# plant_long_life_v1_00.net
KiCad netlist of a schematic drawn in EAGLE
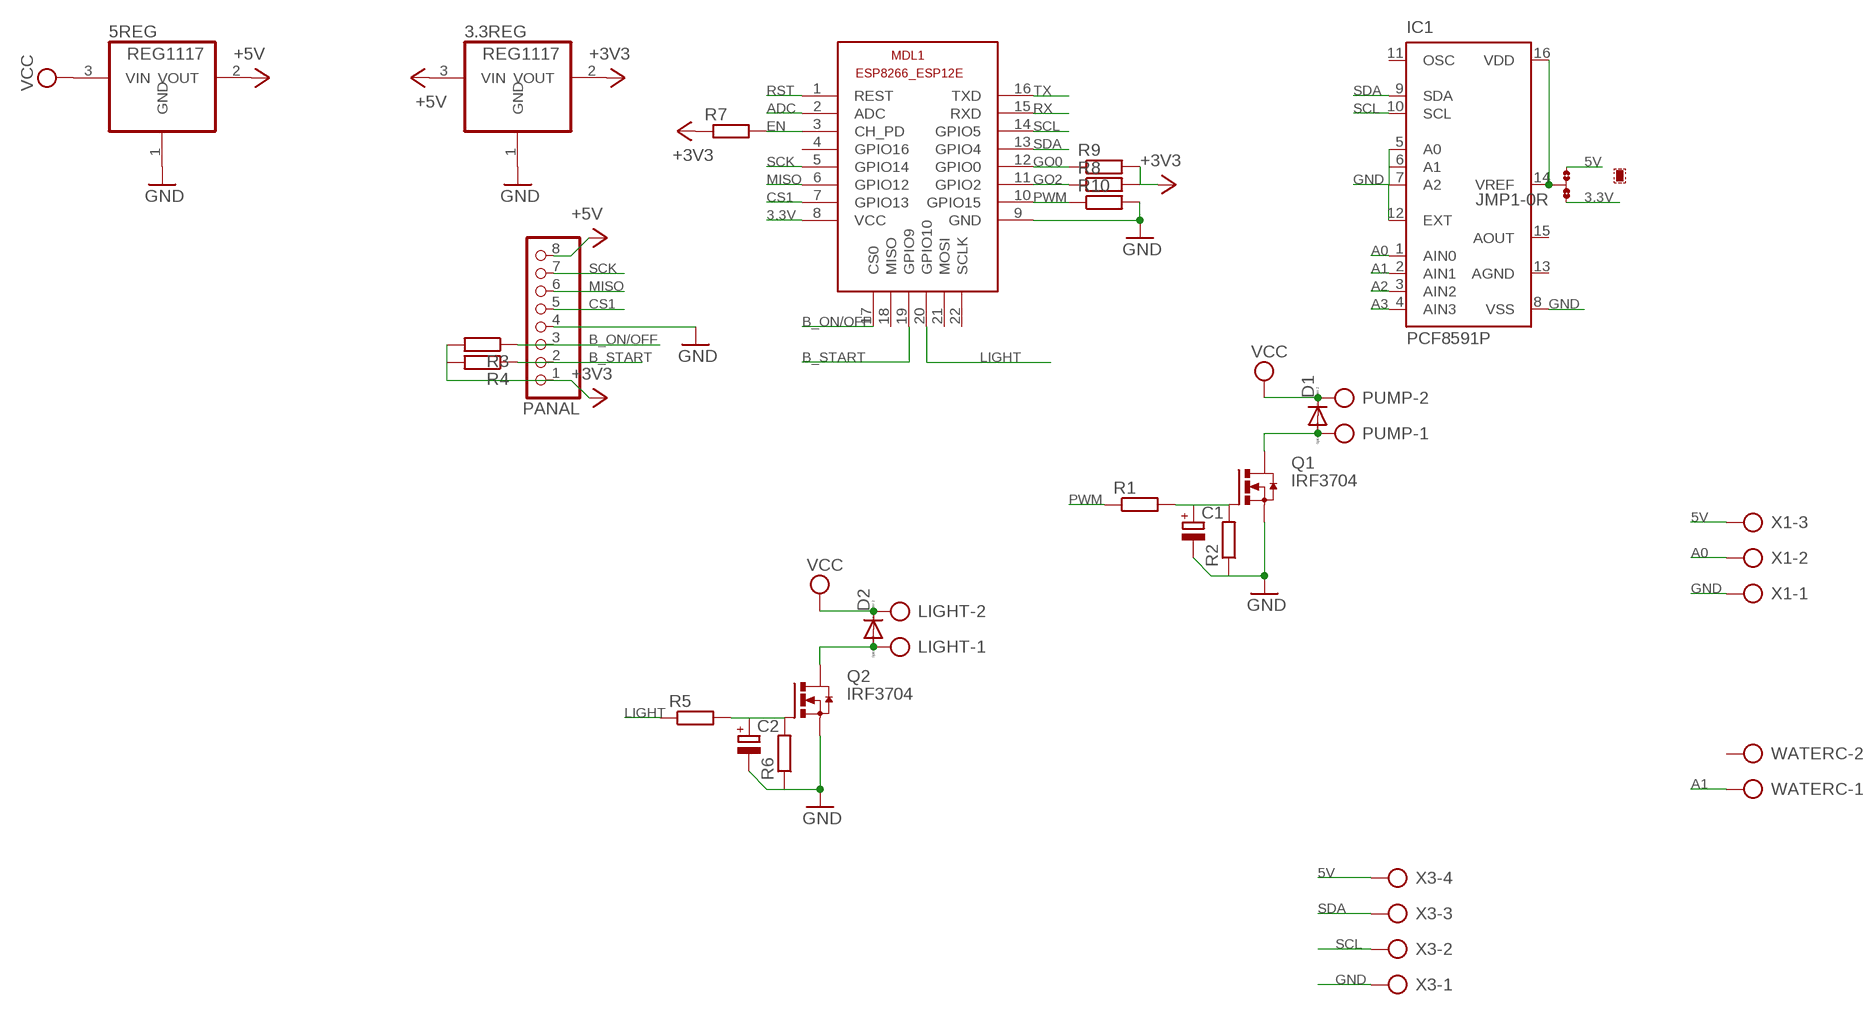
[diagram p0: schematic, sheet 1]

(export (version "E")
  (design (tool "Eeschema 10.0.6"))
  (components
    (comp (ref "3.3REG")
      (value "REG1117")
      (footprint "eagle-import:SOT223")
      (libsource (lib "eagle-import") (part "REG1117"))
    )
    (comp (ref "5REG")
      (value "REG1117")
      (footprint "eagle-import:SOT223")
      (libsource (lib "eagle-import") (part "REG1117"))
    )
    (comp (ref "C1")
      (value "CPOL-EUSMCA")
      (footprint "eagle-import:SMC_A")
      (libsource (lib "eagle-import") (part "CPOL-EUSMCA"))
    )
    (comp (ref "C2")
      (value "CPOL-EUSMCA")
      (footprint "eagle-import:SMC_A")
      (libsource (lib "eagle-import") (part "CPOL-EUSMCA"))
    )
    (comp (ref "D1")
      (value "DIODE-SMC")
      (footprint "eagle-import:SMC")
      (libsource (lib "eagle-import") (part "DIODE-SMC"))
    )
    (comp (ref "D2")
      (value "DIODE-SMC")
      (footprint "eagle-import:SMC")
      (libsource (lib "eagle-import") (part "DIODE-SMC"))
    )
    (comp (ref "IC1")
      (value "PCF8591P")
      (footprint "eagle-import:DIL16")
      (fields (field (name "MF") "FARNELL"))
      (libsource (lib "eagle-import") (part "PCF8591P"))
    )
    (comp (ref "JMP1")
      (value "0R-JUMPA")
      (footprint "eagle-import:A0R-JMP")
      (libsource (lib "eagle-import") (part "0R-JUMPA"))
    )
    (comp (ref "LIGHT")
      (value "AK300/2")
      (footprint "eagle-import:AK300_2")
      (libsource (lib "eagle-import") (part "AK300/2"))
    )
    (comp (ref "MDL1")
      (value "ESP8266-12EESP8266-ESP12E")
      (footprint "eagle-import:ESP8266-ESP12E")
      (libsource (lib "eagle-import") (part "ESP8266-12EESP8266-ESP12E"))
    )
    (comp (ref "PANAL")
      (value "PINHD-1X8")
      (footprint "eagle-import:1X08")
      (libsource (lib "eagle-import") (part "PINHD-1X8"))
    )
    (comp (ref "PUMP")
      (value "AK300/2")
      (footprint "eagle-import:AK300_2")
      (libsource (lib "eagle-import") (part "AK300/2"))
    )
    (comp (ref "Q1")
      (value "IRF3704")
      (footprint "eagle-import:TO220AH")
      (libsource (lib "eagle-import") (part "IRF3704"))
    )
    (comp (ref "Q2")
      (value "IRF3704")
      (footprint "eagle-import:TO220AH")
      (libsource (lib "eagle-import") (part "IRF3704"))
    )
    (comp (ref "R1")
      (value "R-EU_R0805")
      (footprint "eagle-import:R0805")
      (libsource (lib "eagle-import") (part "R-EU_R0805"))
    )
    (comp (ref "R2")
      (value "R-EU_R0805")
      (footprint "eagle-import:R0805")
      (libsource (lib "eagle-import") (part "R-EU_R0805"))
    )
    (comp (ref "R3")
      (value "R-EU_R0805")
      (footprint "eagle-import:R0805")
      (libsource (lib "eagle-import") (part "R-EU_R0805"))
    )
    (comp (ref "R4")
      (value "R-EU_R0805")
      (footprint "eagle-import:R0805")
      (libsource (lib "eagle-import") (part "R-EU_R0805"))
    )
    (comp (ref "R5")
      (value "R-EU_R0805")
      (footprint "eagle-import:R0805")
      (libsource (lib "eagle-import") (part "R-EU_R0805"))
    )
    (comp (ref "R6")
      (value "R-EU_R0805")
      (footprint "eagle-import:R0805")
      (libsource (lib "eagle-import") (part "R-EU_R0805"))
    )
    (comp (ref "R7")
      (value "R-EU_R0805")
      (footprint "eagle-import:R0805")
      (libsource (lib "eagle-import") (part "R-EU_R0805"))
    )
    (comp (ref "R8")
      (value "R-EU_R0805")
      (footprint "eagle-import:R0805")
      (libsource (lib "eagle-import") (part "R-EU_R0805"))
    )
    (comp (ref "R9")
      (value "R-EU_R0805")
      (footprint "eagle-import:R0805")
      (libsource (lib "eagle-import") (part "R-EU_R0805"))
    )
    (comp (ref "R10")
      (value "R-EU_R0805")
      (footprint "eagle-import:R0805")
      (libsource (lib "eagle-import") (part "R-EU_R0805"))
    )
    (comp (ref "WATERC")
      (value "AK300/2")
      (footprint "eagle-import:AK300_2")
      (libsource (lib "eagle-import") (part "AK300/2"))
    )
    (comp (ref "X1")
      (value "AK500/3")
      (footprint "eagle-import:AK500_3")
      (libsource (lib "eagle-import") (part "AK500/3"))
    )
    (comp (ref "X3")
      (value "AK500/4")
      (footprint "eagle-import:AK500_4")
      (libsource (lib "eagle-import") (part "AK500/4"))
    )
  )
  (nets
    (net (code "1") (name "+3V3") (class "Default")
      (node (ref "3.3REG") (pin "2") (pinfunction "VOUT_2") (pintype "output"))
      (node (ref "PANAL") (pin "1") (pinfunction "1_1") (pintype "passive"))
      (node (ref "R3") (pin "2") (pinfunction "2_2") (pintype "passive"))
      (node (ref "R4") (pin "2") (pinfunction "2_2") (pintype "passive"))
      (node (ref "R7") (pin "1") (pinfunction "1_1") (pintype "passive"))
      (node (ref "R8") (pin "2") (pinfunction "2_2") (pintype "passive"))
      (node (ref "R9") (pin "2") (pinfunction "2_2") (pintype "passive"))
    )
    (net (code "2") (name "+5V") (class "Default")
      (node (ref "3.3REG") (pin "3") (pinfunction "VIN_3") (pintype "input"))
      (node (ref "5REG") (pin "2") (pinfunction "VOUT_2") (pintype "output"))
      (node (ref "PANAL") (pin "8") (pinfunction "8_8") (pintype "passive"))
    )
    (net (code "3") (name "/3.3V") (class "Default")
      (node (ref "JMP1") (pin "1") (pinfunction "1_1") (pintype "passive"))
      (node (ref "MDL1") (pin "8") (pinfunction "VCC_8") (pintype "bidirectional"))
    )
    (net (code "4") (name "/5V") (class "Default")
      (node (ref "JMP1") (pin "3") (pinfunction "3_3") (pintype "passive"))
      (node (ref "X1") (pin "3") (pinfunction "KL_3") (pintype "passive"))
      (node (ref "X3") (pin "4") (pinfunction "KL_4") (pintype "passive"))
    )
    (net (code "5") (name "/A0") (class "Default")
      (node (ref "IC1") (pin "1") (pinfunction "AIN0_1") (pintype "input"))
      (node (ref "X1") (pin "2") (pinfunction "KL_2") (pintype "passive"))
    )
    (net (code "6") (name "/A1") (class "Default")
      (node (ref "IC1") (pin "2") (pinfunction "AIN1_2") (pintype "input"))
      (node (ref "WATERC") (pin "1") (pinfunction "KL_1") (pintype "passive"))
    )
    (net (code "7") (name "/A2") (class "Default")
      (node (ref "IC1") (pin "3") (pinfunction "AIN2_3") (pintype "input"))
    )
    (net (code "8") (name "/A3") (class "Default")
      (node (ref "IC1") (pin "4") (pinfunction "AIN3_4") (pintype "input"))
    )
    (net (code "9") (name "/ADC") (class "Default")
      (node (ref "MDL1") (pin "2") (pinfunction "ADC_2") (pintype "bidirectional"))
    )
    (net (code "10") (name "/AGND") (class "Default")
      (node (ref "IC1") (pin "13") (pinfunction "AGND_13") (pintype "power_in"))
    )
    (net (code "11") (name "/B_ON{slash}OFF") (class "Default")
      (node (ref "MDL1") (pin "17") (pinfunction "CS0_17") (pintype "bidirectional"))
      (node (ref "PANAL") (pin "3") (pinfunction "3_3") (pintype "passive"))
      (node (ref "R3") (pin "1") (pinfunction "1_1") (pintype "passive"))
    )
    (net (code "12") (name "/B_START") (class "Default")
      (node (ref "MDL1") (pin "19") (pinfunction "GPIO9_19") (pintype "bidirectional"))
      (node (ref "PANAL") (pin "2") (pinfunction "2_2") (pintype "passive"))
      (node (ref "R4") (pin "1") (pinfunction "1_1") (pintype "passive"))
    )
    (net (code "13") (name "/CS1") (class "Default")
      (node (ref "MDL1") (pin "7") (pinfunction "GPIO13_7") (pintype "bidirectional"))
      (node (ref "PANAL") (pin "5") (pinfunction "5_5") (pintype "passive"))
    )
    (net (code "14") (name "/EN") (class "Default")
      (node (ref "MDL1") (pin "3") (pinfunction "CH_PD_3") (pintype "bidirectional"))
      (node (ref "R7") (pin "2") (pinfunction "2_2") (pintype "passive"))
    )
    (net (code "15") (name "/GO0") (class "Default")
      (node (ref "MDL1") (pin "12") (pinfunction "GPIO0_12") (pintype "bidirectional"))
      (node (ref "R9") (pin "1") (pinfunction "1_1") (pintype "passive"))
    )
    (net (code "16") (name "/GO2") (class "Default")
      (node (ref "MDL1") (pin "11") (pinfunction "GPIO2_11") (pintype "bidirectional"))
      (node (ref "R8") (pin "1") (pinfunction "1_1") (pintype "passive"))
    )
    (net (code "17") (name "/LIGHT") (class "Default")
      (node (ref "MDL1") (pin "20") (pinfunction "GPIO10_20") (pintype "bidirectional"))
      (node (ref "R5") (pin "1") (pinfunction "1_1") (pintype "passive"))
    )
    (net (code "18") (name "/MISO") (class "Default")
      (node (ref "MDL1") (pin "6") (pinfunction "GPIO12_6") (pintype "bidirectional"))
      (node (ref "PANAL") (pin "6") (pinfunction "6_6") (pintype "passive"))
    )
    (net (code "19") (name "/PWM") (class "Default")
      (node (ref "MDL1") (pin "10") (pinfunction "GPIO15_10") (pintype "bidirectional"))
      (node (ref "R1") (pin "1") (pinfunction "1_1") (pintype "passive"))
      (node (ref "R10") (pin "1") (pinfunction "1_1") (pintype "passive"))
    )
    (net (code "20") (name "/RST") (class "Default")
      (node (ref "MDL1") (pin "1") (pinfunction "REST_1") (pintype "bidirectional"))
    )
    (net (code "21") (name "/RX") (class "Default")
      (node (ref "MDL1") (pin "15") (pinfunction "RXD_15") (pintype "bidirectional"))
    )
    (net (code "22") (name "/SCK") (class "Default")
      (node (ref "MDL1") (pin "5") (pinfunction "GPIO14_5") (pintype "bidirectional"))
      (node (ref "PANAL") (pin "7") (pinfunction "7_7") (pintype "passive"))
    )
    (net (code "23") (name "/SCL") (class "Default")
      (node (ref "IC1") (pin "10") (pinfunction "SCL_10") (pintype "input"))
      (node (ref "MDL1") (pin "14") (pinfunction "GPIO5_14") (pintype "bidirectional"))
      (node (ref "X3") (pin "2") (pinfunction "KL_2") (pintype "passive"))
    )
    (net (code "24") (name "/SDA") (class "Default")
      (node (ref "IC1") (pin "9") (pinfunction "SDA_9") (pintype "bidirectional"))
      (node (ref "MDL1") (pin "13") (pinfunction "GPIO4_13") (pintype "bidirectional"))
      (node (ref "X3") (pin "3") (pinfunction "KL_3") (pintype "passive"))
    )
    (net (code "25") (name "/TX") (class "Default")
      (node (ref "MDL1") (pin "16") (pinfunction "TXD_16") (pintype "bidirectional"))
    )
    (net (code "26") (name "GND") (class "Default")
      (node (ref "3.3REG") (pin "1") (pinfunction "GND_1") (pintype "power_in"))
      (node (ref "5REG") (pin "1") (pinfunction "GND_1") (pintype "power_in"))
      (node (ref "C1") (pin "-") (pinfunction "-_-") (pintype "passive"))
      (node (ref "C2") (pin "-") (pinfunction "-_-") (pintype "passive"))
      (node (ref "IC1") (pin "12") (pinfunction "EXT_12") (pintype "input"))
      (node (ref "IC1") (pin "5") (pinfunction "A0_5") (pintype "input"))
      (node (ref "IC1") (pin "6") (pinfunction "A1_6") (pintype "input"))
      (node (ref "IC1") (pin "7") (pinfunction "A2_7") (pintype "input"))
      (node (ref "IC1") (pin "8") (pinfunction "VSS_8") (pintype "power_in"))
      (node (ref "MDL1") (pin "9") (pinfunction "GND_9") (pintype "bidirectional"))
      (node (ref "PANAL") (pin "4") (pinfunction "4_4") (pintype "passive"))
      (node (ref "Q1") (pin "E") (pinfunction "S_E") (pintype "passive"))
      (node (ref "Q2") (pin "E") (pinfunction "S_E") (pintype "passive"))
      (node (ref "R10") (pin "2") (pinfunction "2_2") (pintype "passive"))
      (node (ref "R2") (pin "1") (pinfunction "1_1") (pintype "passive"))
      (node (ref "R6") (pin "1") (pinfunction "1_1") (pintype "passive"))
      (node (ref "X1") (pin "1") (pinfunction "KL_1") (pintype "passive"))
      (node (ref "X3") (pin "1") (pinfunction "KL_1") (pintype "passive"))
    )
    (net (code "27") (name "Net-(IC1-VDD)") (class "Default")
      (node (ref "IC1") (pin "14") (pinfunction "VREF_14") (pintype "input"))
      (node (ref "IC1") (pin "16") (pinfunction "VDD_16") (pintype "power_in"))
      (node (ref "JMP1") (pin "2") (pinfunction "2_2") (pintype "passive"))
    )
    (net (code "28") (name "Net-(LIGHTA-KL)") (class "Default")
      (node (ref "D2") (pin "A") (pinfunction "A_A") (pintype "passive"))
      (node (ref "LIGHT") (pin "1") (pinfunction "KL_1") (pintype "passive"))
      (node (ref "Q2") (pin "C") (pinfunction "D_C") (pintype "passive"))
    )
    (net (code "29") (name "Net-(PUMPA-KL)") (class "Default")
      (node (ref "D1") (pin "A") (pinfunction "A_A") (pintype "passive"))
      (node (ref "PUMP") (pin "1") (pinfunction "KL_1") (pintype "passive"))
      (node (ref "Q1") (pin "C") (pinfunction "D_C") (pintype "passive"))
    )
    (net (code "30") (name "Net-(Q1-G)") (class "Default")
      (node (ref "C1") (pin "+") (pinfunction "+_+") (pintype "passive"))
      (node (ref "Q1") (pin "B") (pinfunction "G_B") (pintype "passive"))
      (node (ref "R1") (pin "2") (pinfunction "2_2") (pintype "passive"))
      (node (ref "R2") (pin "2") (pinfunction "2_2") (pintype "passive"))
    )
    (net (code "31") (name "Net-(Q2-G)") (class "Default")
      (node (ref "C2") (pin "+") (pinfunction "+_+") (pintype "passive"))
      (node (ref "Q2") (pin "B") (pinfunction "G_B") (pintype "passive"))
      (node (ref "R5") (pin "2") (pinfunction "2_2") (pintype "passive"))
      (node (ref "R6") (pin "2") (pinfunction "2_2") (pintype "passive"))
    )
    (net (code "32") (name "VCC") (class "Default")
      (node (ref "5REG") (pin "3") (pinfunction "VIN_3") (pintype "input"))
      (node (ref "D1") (pin "C") (pinfunction "C_C") (pintype "passive"))
      (node (ref "D2") (pin "C") (pinfunction "C_C") (pintype "passive"))
      (node (ref "LIGHT") (pin "2") (pinfunction "KL_2") (pintype "passive"))
      (node (ref "PUMP") (pin "2") (pinfunction "KL_2") (pintype "passive"))
    )
    (net (code "33") (name "unconnected-(IC1-AOUT-Pad15)") (class "Default")
      (node (ref "IC1") (pin "15") (pinfunction "AOUT_15") (pintype "output"))
    )
    (net (code "34") (name "unconnected-(IC1-OSC-Pad11)") (class "Default")
      (node (ref "IC1") (pin "11") (pinfunction "OSC_11") (pintype "input"))
    )
    (net (code "35") (name "unconnected-(MDL1-GPIO16-Pad4)") (class "Default")
      (node (ref "MDL1") (pin "4") (pinfunction "GPIO16_4") (pintype "bidirectional"))
    )
    (net (code "36") (name "unconnected-(MDL1-MISO-Pad18)") (class "Default")
      (node (ref "MDL1") (pin "18") (pinfunction "MISO_18") (pintype "bidirectional"))
    )
    (net (code "37") (name "unconnected-(MDL1-MOSI-Pad21)") (class "Default")
      (node (ref "MDL1") (pin "21") (pinfunction "MOSI_21") (pintype "bidirectional"))
    )
    (net (code "38") (name "unconnected-(MDL1-SCLK-Pad22)") (class "Default")
      (node (ref "MDL1") (pin "22") (pinfunction "SCLK_22") (pintype "bidirectional"))
    )
    (net (code "39") (name "unconnected-(WATERCB-KL-Pad2)") (class "Default")
      (node (ref "WATERC") (pin "2") (pinfunction "KL_2") (pintype "passive"))
    )
  )
)
